# LSM6DSMTR.net
KiCad netlist of a schematic drawn in Altium Designer
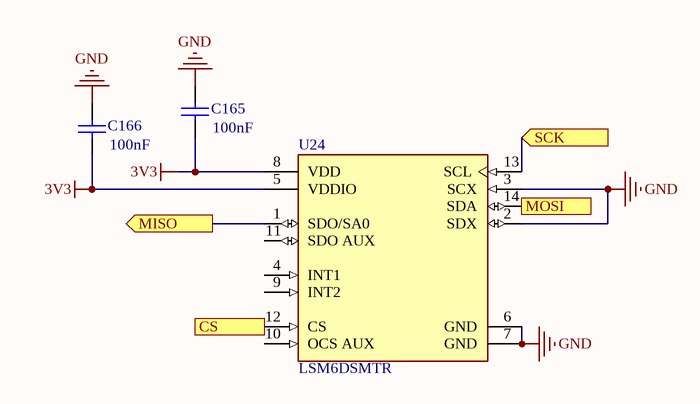
[diagram p0: LSM6DSMTR.SchDoc]

(export (version "E")
  (design (tool "Eeschema 10.0.6"))
  (components
    (comp (ref "C165")
      (value "100nF")
      (footprint "0402-A")
      (description "Capacitor")
      (fields (field (name "Comment") "Cap") (field (name "PUBLISHER") "Altium Limited"))
      (libsource (lib "Miscellaneous Devices") (part "Cap"))
    )
    (comp (ref "C166")
      (value "100nF")
      (footprint "0402-A")
      (description "Capacitor")
      (fields (field (name "Comment") "Cap") (field (name "PUBLISHER") "Altium Limited"))
      (libsource (lib "Miscellaneous Devices") (part "Cap"))
    )
    (comp (ref "U24")
      (value "LSM6DSMTR")
      (footprint "FP-LGA-14L-DM00249496-MFG")
      (description "IMU ACCEL/GYRO I2C/SPI 14LGA")
      (fields
        (field (name "OCTOPART") "https://octopart.com/lsm6dsmtr-stmicroelectronics-66358194")
        (field (name "MANUFACTURER") "STMicroelectronics")
      )
      (libsource (lib "Altium Content Vault") (part "dd82ae232bae541fa9c740d21cb9072"))
    )
  )
  (nets
    (net (code "1") (name "/CS") (class "Default")
      (node (ref "U24") (pin "12") (pinfunction "CS_12") (pintype "input"))
    )
    (net (code "2") (name "/MISO") (class "Default")
      (node (ref "U24") (pin "1") (pinfunction "SDO/SA0_1") (pintype "bidirectional"))
    )
    (net (code "3") (name "/MOSI") (class "Default")
      (node (ref "U24") (pin "14") (pinfunction "SDA_14") (pintype "bidirectional"))
    )
    (net (code "4") (name "/SCK") (class "Default")
      (node (ref "U24") (pin "13") (pinfunction "SCL_13") (pintype "input"))
    )
    (net (code "5") (name "3V3") (class "Default")
      (node (ref "C165") (pin "2") (pinfunction "2_2") (pintype "passive"))
      (node (ref "C166") (pin "2") (pinfunction "2_2") (pintype "passive"))
      (node (ref "U24") (pin "5") (pinfunction "VDDIO_5") (pintype "power_in"))
      (node (ref "U24") (pin "8") (pinfunction "VDD_8") (pintype "power_in"))
    )
    (net (code "6") (name "GND") (class "Default")
      (node (ref "C165") (pin "1") (pinfunction "1_1") (pintype "passive"))
      (node (ref "C166") (pin "1") (pinfunction "1_1") (pintype "passive"))
      (node (ref "U24") (pin "2") (pinfunction "SDX_2") (pintype "bidirectional"))
      (node (ref "U24") (pin "3") (pinfunction "SCX_3") (pintype "input"))
      (node (ref "U24") (pin "6") (pinfunction "GND_6") (pintype "power_in"))
      (node (ref "U24") (pin "7") (pinfunction "GND_7") (pintype "power_in"))
    )
    (net (code "7") (name "unconnected-(U24-INT1-Pad4)") (class "Default")
      (node (ref "U24") (pin "4") (pinfunction "INT1_4") (pintype "input"))
    )
    (net (code "8") (name "unconnected-(U24-INT2-Pad9)") (class "Default")
      (node (ref "U24") (pin "9") (pinfunction "INT2_9") (pintype "input"))
    )
    (net (code "9") (name "unconnected-(U24-OCS_AUX-Pad10)") (class "Default")
      (node (ref "U24") (pin "10") (pinfunction "OCS_AUX_10") (pintype "input"))
    )
    (net (code "10") (name "unconnected-(U24-SDO_AUX-Pad11)") (class "Default")
      (node (ref "U24") (pin "11") (pinfunction "SDO_AUX_11") (pintype "bidirectional"))
    )
  )
)
